# tube-tester.net
KiCad netlist of a schematic drawn in EAGLE
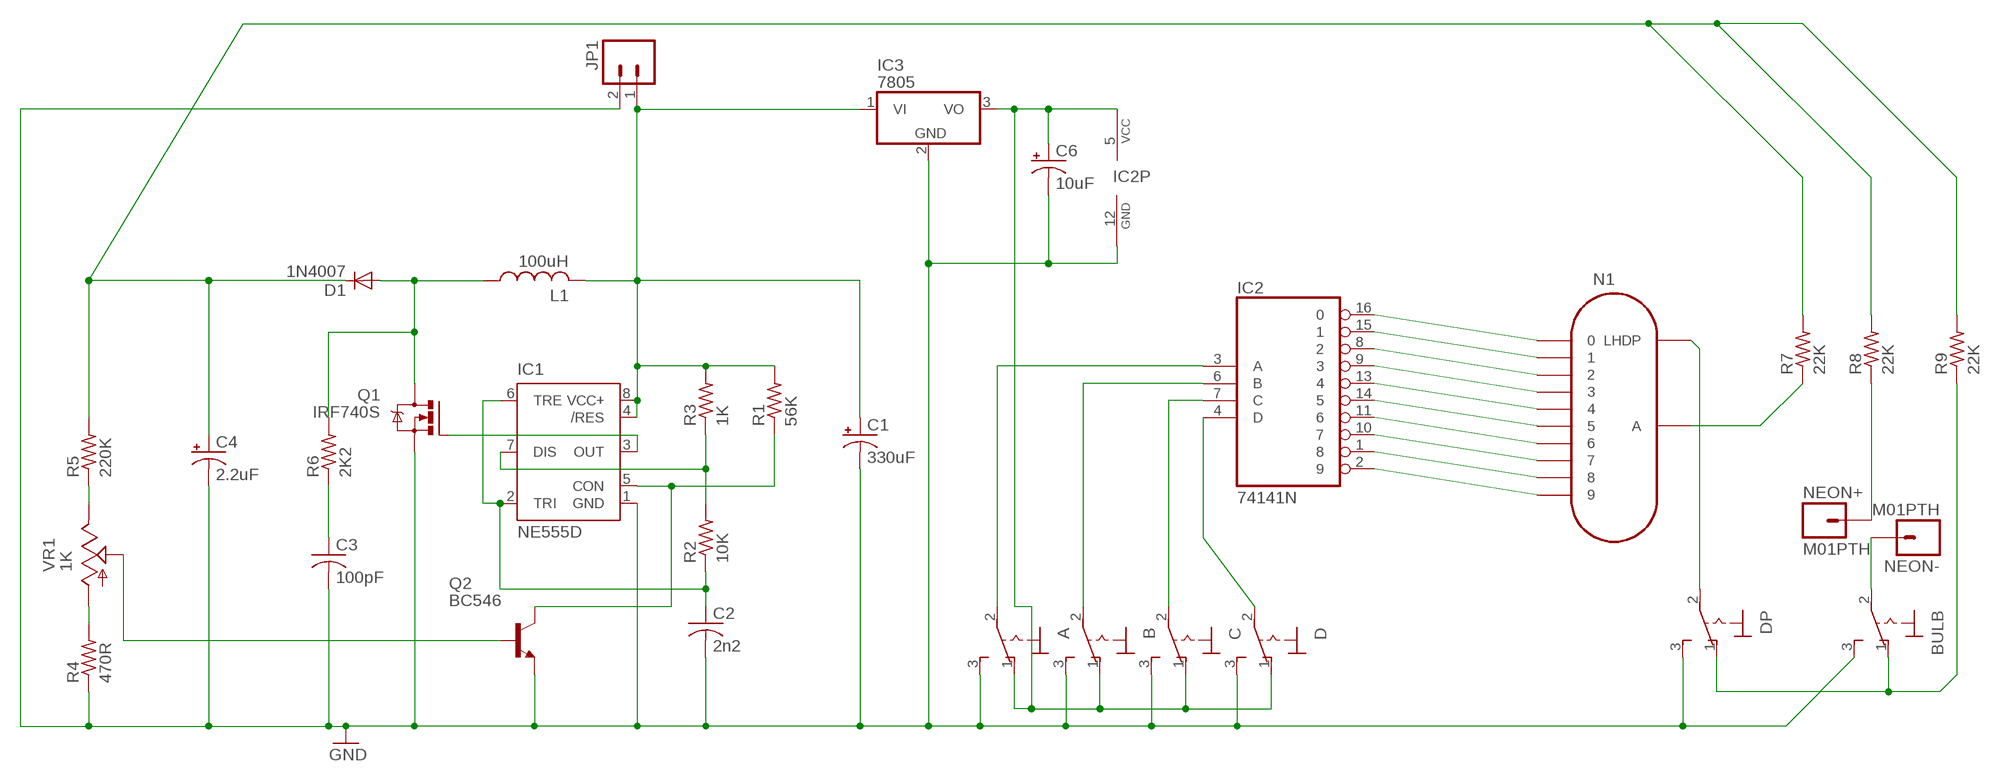
[diagram p0: schematic, sheet 1]

(export (version "E")
  (design (tool "Eeschema 10.0.6"))
  (components
    (comp (ref "A")
      (value "320-916")
      (footprint "eagle-import:320-916")
      (libsource (lib "eagle-import") (part "320-916"))
    )
    (comp (ref "B")
      (value "320-916")
      (footprint "eagle-import:320-916")
      (libsource (lib "eagle-import") (part "320-916"))
    )
    (comp (ref "BULB")
      (value "320-916")
      (footprint "eagle-import:320-916")
      (libsource (lib "eagle-import") (part "320-916"))
    )
    (comp (ref "C")
      (value "320-916")
      (footprint "eagle-import:320-916")
      (libsource (lib "eagle-import") (part "320-916"))
    )
    (comp (ref "C1")
      (value "330uF")
      (footprint "eagle-import:E5-10,5")
      (libsource (lib "eagle-import") (part "CAPACITOR_POLE5-10.5"))
    )
    (comp (ref "C2")
      (value "2n2")
      (footprint "eagle-import:C1206K")
      (libsource (lib "eagle-import") (part "CAPACITORC1206K"))
    )
    (comp (ref "C3")
      (value "100pF")
      (footprint "eagle-import:C1206K")
      (libsource (lib "eagle-import") (part "CAPACITORC1206K"))
    )
    (comp (ref "C4")
      (value "2.2uF")
      (footprint "eagle-import:E3,5-8")
      (libsource (lib "eagle-import") (part "CAPACITOR_POLE3.5-8"))
    )
    (comp (ref "C6")
      (value "10uF")
      (footprint "eagle-import:E2-5")
      (libsource (lib "eagle-import") (part "CAPACITOR_POLE2-5"))
    )
    (comp (ref "D")
      (value "320-916")
      (footprint "eagle-import:320-916")
      (libsource (lib "eagle-import") (part "320-916"))
    )
    (comp (ref "D1")
      (value "1N4007")
      (footprint "eagle-import:SMA-DIODE")
      (libsource (lib "eagle-import") (part "DIODESMA"))
    )
    (comp (ref "DP")
      (value "320-916")
      (footprint "eagle-import:320-916")
      (libsource (lib "eagle-import") (part "320-916"))
    )
    (comp (ref "IC1")
      (value "NE555D")
      (footprint "eagle-import:SO08")
      (libsource (lib "eagle-import") (part "NE555D"))
    )
    (comp (ref "IC2")
      (value "74141N")
      (footprint "eagle-import:DIL16")
      (libsource (lib "eagle-import") (part "74141N"))
    )
    (comp (ref "IC3")
      (value "7805")
      (footprint "eagle-import:TO220H")
      (libsource (lib "eagle-import") (part "78T05"))
    )
    (comp (ref "JP1")
      (value "M023.5MM")
      (footprint "eagle-import:SCREWTERMINAL-3.5MM-2")
      (libsource (lib "eagle-import") (part "M023.5MM"))
    )
    (comp (ref "L1")
      (value "100uH")
      (footprint "eagle-import:0207_10")
      (libsource (lib "eagle-import") (part "INDUCTOR0207/10"))
    )
    (comp (ref "N1")
      (value "IN-12B")
      (footprint "eagle-import:IN-12")
      (libsource (lib "eagle-import") (part "IN-12B"))
    )
    (comp (ref "NEON+")
      (value "M01PTH")
      (footprint "eagle-import:1X01")
      (libsource (lib "eagle-import") (part "M01PTH"))
    )
    (comp (ref "NEON-")
      (value "M01PTH")
      (footprint "eagle-import:1X01")
      (libsource (lib "eagle-import") (part "M01PTH"))
    )
    (comp (ref "Q1")
      (value "IRF740S")
      (footprint "eagle-import:TO263")
      (libsource (lib "eagle-import") (part "IRF740S"))
    )
    (comp (ref "Q2")
      (value "BC546")
      (footprint "eagle-import:TO92-EBC")
      (libsource (lib "eagle-import") (part "BC546A"))
    )
    (comp (ref "R1")
      (value "56K")
      (footprint "eagle-import:R1206")
      (libsource (lib "eagle-import") (part "RESISTORR1206"))
    )
    (comp (ref "R2")
      (value "10K")
      (footprint "eagle-import:R1206")
      (libsource (lib "eagle-import") (part "RESISTORR1206"))
    )
    (comp (ref "R3")
      (value "1K")
      (footprint "eagle-import:R1206")
      (libsource (lib "eagle-import") (part "RESISTORR1206"))
    )
    (comp (ref "R4")
      (value "470R")
      (footprint "eagle-import:0207_10")
      (libsource (lib "eagle-import") (part "RESISTOR0207/10"))
    )
    (comp (ref "R5")
      (value "220K")
      (footprint "eagle-import:0207_10")
      (libsource (lib "eagle-import") (part "RESISTOR0207/10"))
    )
    (comp (ref "R6")
      (value "2K2")
      (footprint "eagle-import:R1206")
      (libsource (lib "eagle-import") (part "RESISTORR1206"))
    )
    (comp (ref "R7")
      (value "22K")
      (footprint "eagle-import:0207_10")
      (libsource (lib "eagle-import") (part "RESISTOR0207/10"))
    )
    (comp (ref "R8")
      (value "22K")
      (footprint "eagle-import:0207_10")
      (libsource (lib "eagle-import") (part "RESISTOR0207/10"))
    )
    (comp (ref "R9")
      (value "22K")
      (footprint "eagle-import:0207_10")
      (libsource (lib "eagle-import") (part "RESISTOR0207/10"))
    )
    (comp (ref "VR1")
      (value "1K")
      (footprint "eagle-import:CA6V")
      (libsource (lib "eagle-import") (part "TRIM_POTCA6V"))
    )
  )
  (nets
    (net (code "1") (name "GND") (class "Default")
      (node (ref "A") (pin "3") (pinfunction "S_3") (pintype "passive"))
      (node (ref "B") (pin "3") (pinfunction "S_3") (pintype "passive"))
      (node (ref "BULB") (pin "3") (pinfunction "S_3") (pintype "passive"))
      (node (ref "C") (pin "3") (pinfunction "S_3") (pintype "passive"))
      (node (ref "C1") (pin "-") (pinfunction "-_-") (pintype "passive"))
      (node (ref "C2") (pin "2") (pinfunction "2_2") (pintype "passive"))
      (node (ref "C3") (pin "2") (pinfunction "2_2") (pintype "passive"))
      (node (ref "C4") (pin "-") (pinfunction "-_-") (pintype "passive"))
      (node (ref "C6") (pin "-") (pinfunction "-_-") (pintype "passive"))
      (node (ref "D") (pin "3") (pinfunction "S_3") (pintype "passive"))
      (node (ref "DP") (pin "3") (pinfunction "S_3") (pintype "passive"))
      (node (ref "IC1") (pin "1") (pinfunction "GND_1") (pintype "power_in"))
      (node (ref "IC2") (pin "12") (pinfunction "GND_12") (pintype "power_in"))
      (node (ref "IC3") (pin "2") (pinfunction "GND_2") (pintype "passive"))
      (node (ref "JP1") (pin "2") (pinfunction "2_2") (pintype "passive"))
      (node (ref "Q1") (pin "2") (pinfunction "S_2") (pintype "passive"))
      (node (ref "Q2") (pin "E") (pinfunction "E_E") (pintype "passive"))
      (node (ref "R4") (pin "1") (pinfunction "1_1") (pintype "passive"))
    )
    (net (code "2") (name "Net-(A-O)") (class "Default")
      (node (ref "A") (pin "1") (pinfunction "O_1") (pintype "passive"))
      (node (ref "B") (pin "1") (pinfunction "O_1") (pintype "passive"))
      (node (ref "C") (pin "1") (pinfunction "O_1") (pintype "passive"))
      (node (ref "C6") (pin "+") (pinfunction "+_+") (pintype "passive"))
      (node (ref "D") (pin "1") (pinfunction "O_1") (pintype "passive"))
      (node (ref "IC2") (pin "5") (pinfunction "VCC_5") (pintype "power_in"))
      (node (ref "IC3") (pin "3") (pinfunction "VO_3") (pintype "passive"))
    )
    (net (code "3") (name "Net-(A-P)") (class "Default")
      (node (ref "A") (pin "2") (pinfunction "P_2") (pintype "passive"))
      (node (ref "IC2") (pin "3") (pinfunction "A_3") (pintype "input"))
    )
    (net (code "4") (name "Net-(B-P)") (class "Default")
      (node (ref "B") (pin "2") (pinfunction "P_2") (pintype "passive"))
      (node (ref "IC2") (pin "6") (pinfunction "B_6") (pintype "input"))
    )
    (net (code "5") (name "Net-(BULB-O)") (class "Default")
      (node (ref "BULB") (pin "1") (pinfunction "O_1") (pintype "passive"))
      (node (ref "DP") (pin "1") (pinfunction "O_1") (pintype "passive"))
      (node (ref "R9") (pin "1") (pinfunction "1_1") (pintype "passive"))
    )
    (net (code "6") (name "Net-(BULB-P)") (class "Default")
      (node (ref "BULB") (pin "2") (pinfunction "P_2") (pintype "passive"))
      (node (ref "NEON-") (pin "1") (pinfunction "1_1") (pintype "passive"))
    )
    (net (code "7") (name "Net-(C-P)") (class "Default")
      (node (ref "C") (pin "2") (pinfunction "P_2") (pintype "passive"))
      (node (ref "IC2") (pin "7") (pinfunction "C_7") (pintype "input"))
    )
    (net (code "8") (name "Net-(C3-Pad1)") (class "Default")
      (node (ref "C3") (pin "1") (pinfunction "1_1") (pintype "passive"))
      (node (ref "R6") (pin "1") (pinfunction "1_1") (pintype "passive"))
    )
    (net (code "9") (name "Net-(C4-Pad+)") (class "Default")
      (node (ref "C4") (pin "+") (pinfunction "+_+") (pintype "passive"))
      (node (ref "D1") (pin "C") (pinfunction "C_C") (pintype "passive"))
      (node (ref "R5") (pin "2") (pinfunction "2_2") (pintype "passive"))
      (node (ref "R7") (pin "2") (pinfunction "2_2") (pintype "passive"))
      (node (ref "R8") (pin "2") (pinfunction "2_2") (pintype "passive"))
      (node (ref "R9") (pin "2") (pinfunction "2_2") (pintype "passive"))
    )
    (net (code "10") (name "Net-(D-P)") (class "Default")
      (node (ref "D") (pin "2") (pinfunction "P_2") (pintype "passive"))
      (node (ref "IC2") (pin "4") (pinfunction "D_4") (pintype "input"))
    )
    (net (code "11") (name "Net-(DP-P)") (class "Default")
      (node (ref "DP") (pin "2") (pinfunction "P_2") (pintype "passive"))
      (node (ref "N1") (pin "LHDP") (pinfunction "LHDP_LHDP") (pintype "bidirectional"))
    )
    (net (code "12") (name "Net-(IC1-CON)") (class "Default")
      (node (ref "IC1") (pin "5") (pinfunction "CON_5") (pintype "input"))
      (node (ref "Q2") (pin "C") (pinfunction "C_C") (pintype "passive"))
      (node (ref "R1") (pin "1") (pinfunction "1_1") (pintype "passive"))
    )
    (net (code "13") (name "Net-(IC1-DIS)") (class "Default")
      (node (ref "IC1") (pin "7") (pinfunction "DIS_7") (pintype "input"))
      (node (ref "R2") (pin "2") (pinfunction "2_2") (pintype "passive"))
      (node (ref "R3") (pin "1") (pinfunction "1_1") (pintype "passive"))
    )
    (net (code "14") (name "Net-(IC1-OUT)") (class "Default")
      (node (ref "IC1") (pin "3") (pinfunction "OUT_3") (pintype "output"))
      (node (ref "Q1") (pin "1") (pinfunction "G_1") (pintype "passive"))
    )
    (net (code "15") (name "Net-(IC1-TRE)") (class "Default")
      (node (ref "C2") (pin "1") (pinfunction "1_1") (pintype "passive"))
      (node (ref "IC1") (pin "2") (pinfunction "TRI_2") (pintype "input"))
      (node (ref "IC1") (pin "6") (pinfunction "TRE_6") (pintype "input"))
      (node (ref "R2") (pin "1") (pinfunction "1_1") (pintype "passive"))
    )
    (net (code "16") (name "Net-(IC1-VCC+)") (class "Default")
      (node (ref "C1") (pin "+") (pinfunction "+_+") (pintype "passive"))
      (node (ref "IC1") (pin "4") (pinfunction "/RES_4") (pintype "input"))
      (node (ref "IC1") (pin "8") (pinfunction "VCC+_8") (pintype "power_in"))
      (node (ref "IC3") (pin "1") (pinfunction "VI_1") (pintype "input"))
      (node (ref "JP1") (pin "1") (pinfunction "1_1") (pintype "passive"))
      (node (ref "L1") (pin "2") (pinfunction "2_2") (pintype "passive"))
      (node (ref "R1") (pin "2") (pinfunction "2_2") (pintype "passive"))
      (node (ref "R3") (pin "2") (pinfunction "2_2") (pintype "passive"))
    )
    (net (code "17") (name "Net-(IC2A-0)") (class "Default")
      (node (ref "IC2") (pin "16") (pinfunction "0_16") (pintype "open_collector"))
      (node (ref "N1") (pin "0") (pinfunction "0_0") (pintype "bidirectional"))
    )
    (net (code "18") (name "Net-(IC2A-1)") (class "Default")
      (node (ref "IC2") (pin "15") (pinfunction "1_15") (pintype "open_collector"))
      (node (ref "N1") (pin "1") (pinfunction "1_1") (pintype "bidirectional"))
    )
    (net (code "19") (name "Net-(IC2A-2)") (class "Default")
      (node (ref "IC2") (pin "8") (pinfunction "2_8") (pintype "open_collector"))
      (node (ref "N1") (pin "2") (pinfunction "2_2") (pintype "bidirectional"))
    )
    (net (code "20") (name "Net-(IC2A-3)") (class "Default")
      (node (ref "IC2") (pin "9") (pinfunction "3_9") (pintype "open_collector"))
      (node (ref "N1") (pin "3") (pinfunction "3_3") (pintype "bidirectional"))
    )
    (net (code "21") (name "Net-(IC2A-4)") (class "Default")
      (node (ref "IC2") (pin "13") (pinfunction "4_13") (pintype "open_collector"))
      (node (ref "N1") (pin "4") (pinfunction "4_4") (pintype "bidirectional"))
    )
    (net (code "22") (name "Net-(IC2A-5)") (class "Default")
      (node (ref "IC2") (pin "14") (pinfunction "5_14") (pintype "open_collector"))
      (node (ref "N1") (pin "5") (pinfunction "5_5") (pintype "bidirectional"))
    )
    (net (code "23") (name "Net-(IC2A-6)") (class "Default")
      (node (ref "IC2") (pin "11") (pinfunction "6_11") (pintype "open_collector"))
      (node (ref "N1") (pin "6") (pinfunction "6_6") (pintype "bidirectional"))
    )
    (net (code "24") (name "Net-(IC2A-7)") (class "Default")
      (node (ref "IC2") (pin "10") (pinfunction "7_10") (pintype "open_collector"))
      (node (ref "N1") (pin "7") (pinfunction "7_7") (pintype "bidirectional"))
    )
    (net (code "25") (name "Net-(IC2A-8)") (class "Default")
      (node (ref "IC2") (pin "1") (pinfunction "8_1") (pintype "open_collector"))
      (node (ref "N1") (pin "8") (pinfunction "8_8") (pintype "bidirectional"))
    )
    (net (code "26") (name "Net-(IC2A-9)") (class "Default")
      (node (ref "IC2") (pin "2") (pinfunction "9_2") (pintype "open_collector"))
      (node (ref "N1") (pin "9") (pinfunction "9_9") (pintype "bidirectional"))
    )
    (net (code "27") (name "Net-(N1-PadA)") (class "Default")
      (node (ref "N1") (pin "A") (pinfunction "A_A") (pintype "bidirectional"))
      (node (ref "R7") (pin "1") (pinfunction "1_1") (pintype "passive"))
    )
    (net (code "28") (name "Net-(NEON+-Pad1)") (class "Default")
      (node (ref "NEON+") (pin "1") (pinfunction "1_1") (pintype "passive"))
      (node (ref "R8") (pin "1") (pinfunction "1_1") (pintype "passive"))
    )
    (net (code "29") (name "Net-(Q1-D)") (class "Default")
      (node (ref "D1") (pin "A") (pinfunction "A_A") (pintype "passive"))
      (node (ref "L1") (pin "1") (pinfunction "1_1") (pintype "passive"))
      (node (ref "Q1") (pin "3") (pinfunction "D_3") (pintype "passive"))
      (node (ref "R6") (pin "2") (pinfunction "2_2") (pintype "passive"))
    )
    (net (code "30") (name "Net-(Q2-PadB)") (class "Default")
      (node (ref "Q2") (pin "B") (pinfunction "B_B") (pintype "passive"))
      (node (ref "VR1") (pin "S") (pinfunction "S_S") (pintype "passive"))
    )
    (net (code "31") (name "Net-(R4-Pad2)") (class "Default")
      (node (ref "R4") (pin "2") (pinfunction "2_2") (pintype "passive"))
      (node (ref "VR1") (pin "A") (pinfunction "A_A") (pintype "passive"))
    )
    (net (code "32") (name "Net-(R5-Pad1)") (class "Default")
      (node (ref "R5") (pin "1") (pinfunction "1_1") (pintype "passive"))
      (node (ref "VR1") (pin "E") (pinfunction "E_E") (pintype "passive"))
    )
  )
)
